# circuit.net
KiCad netlist of a schematic drawn in Altium Designer
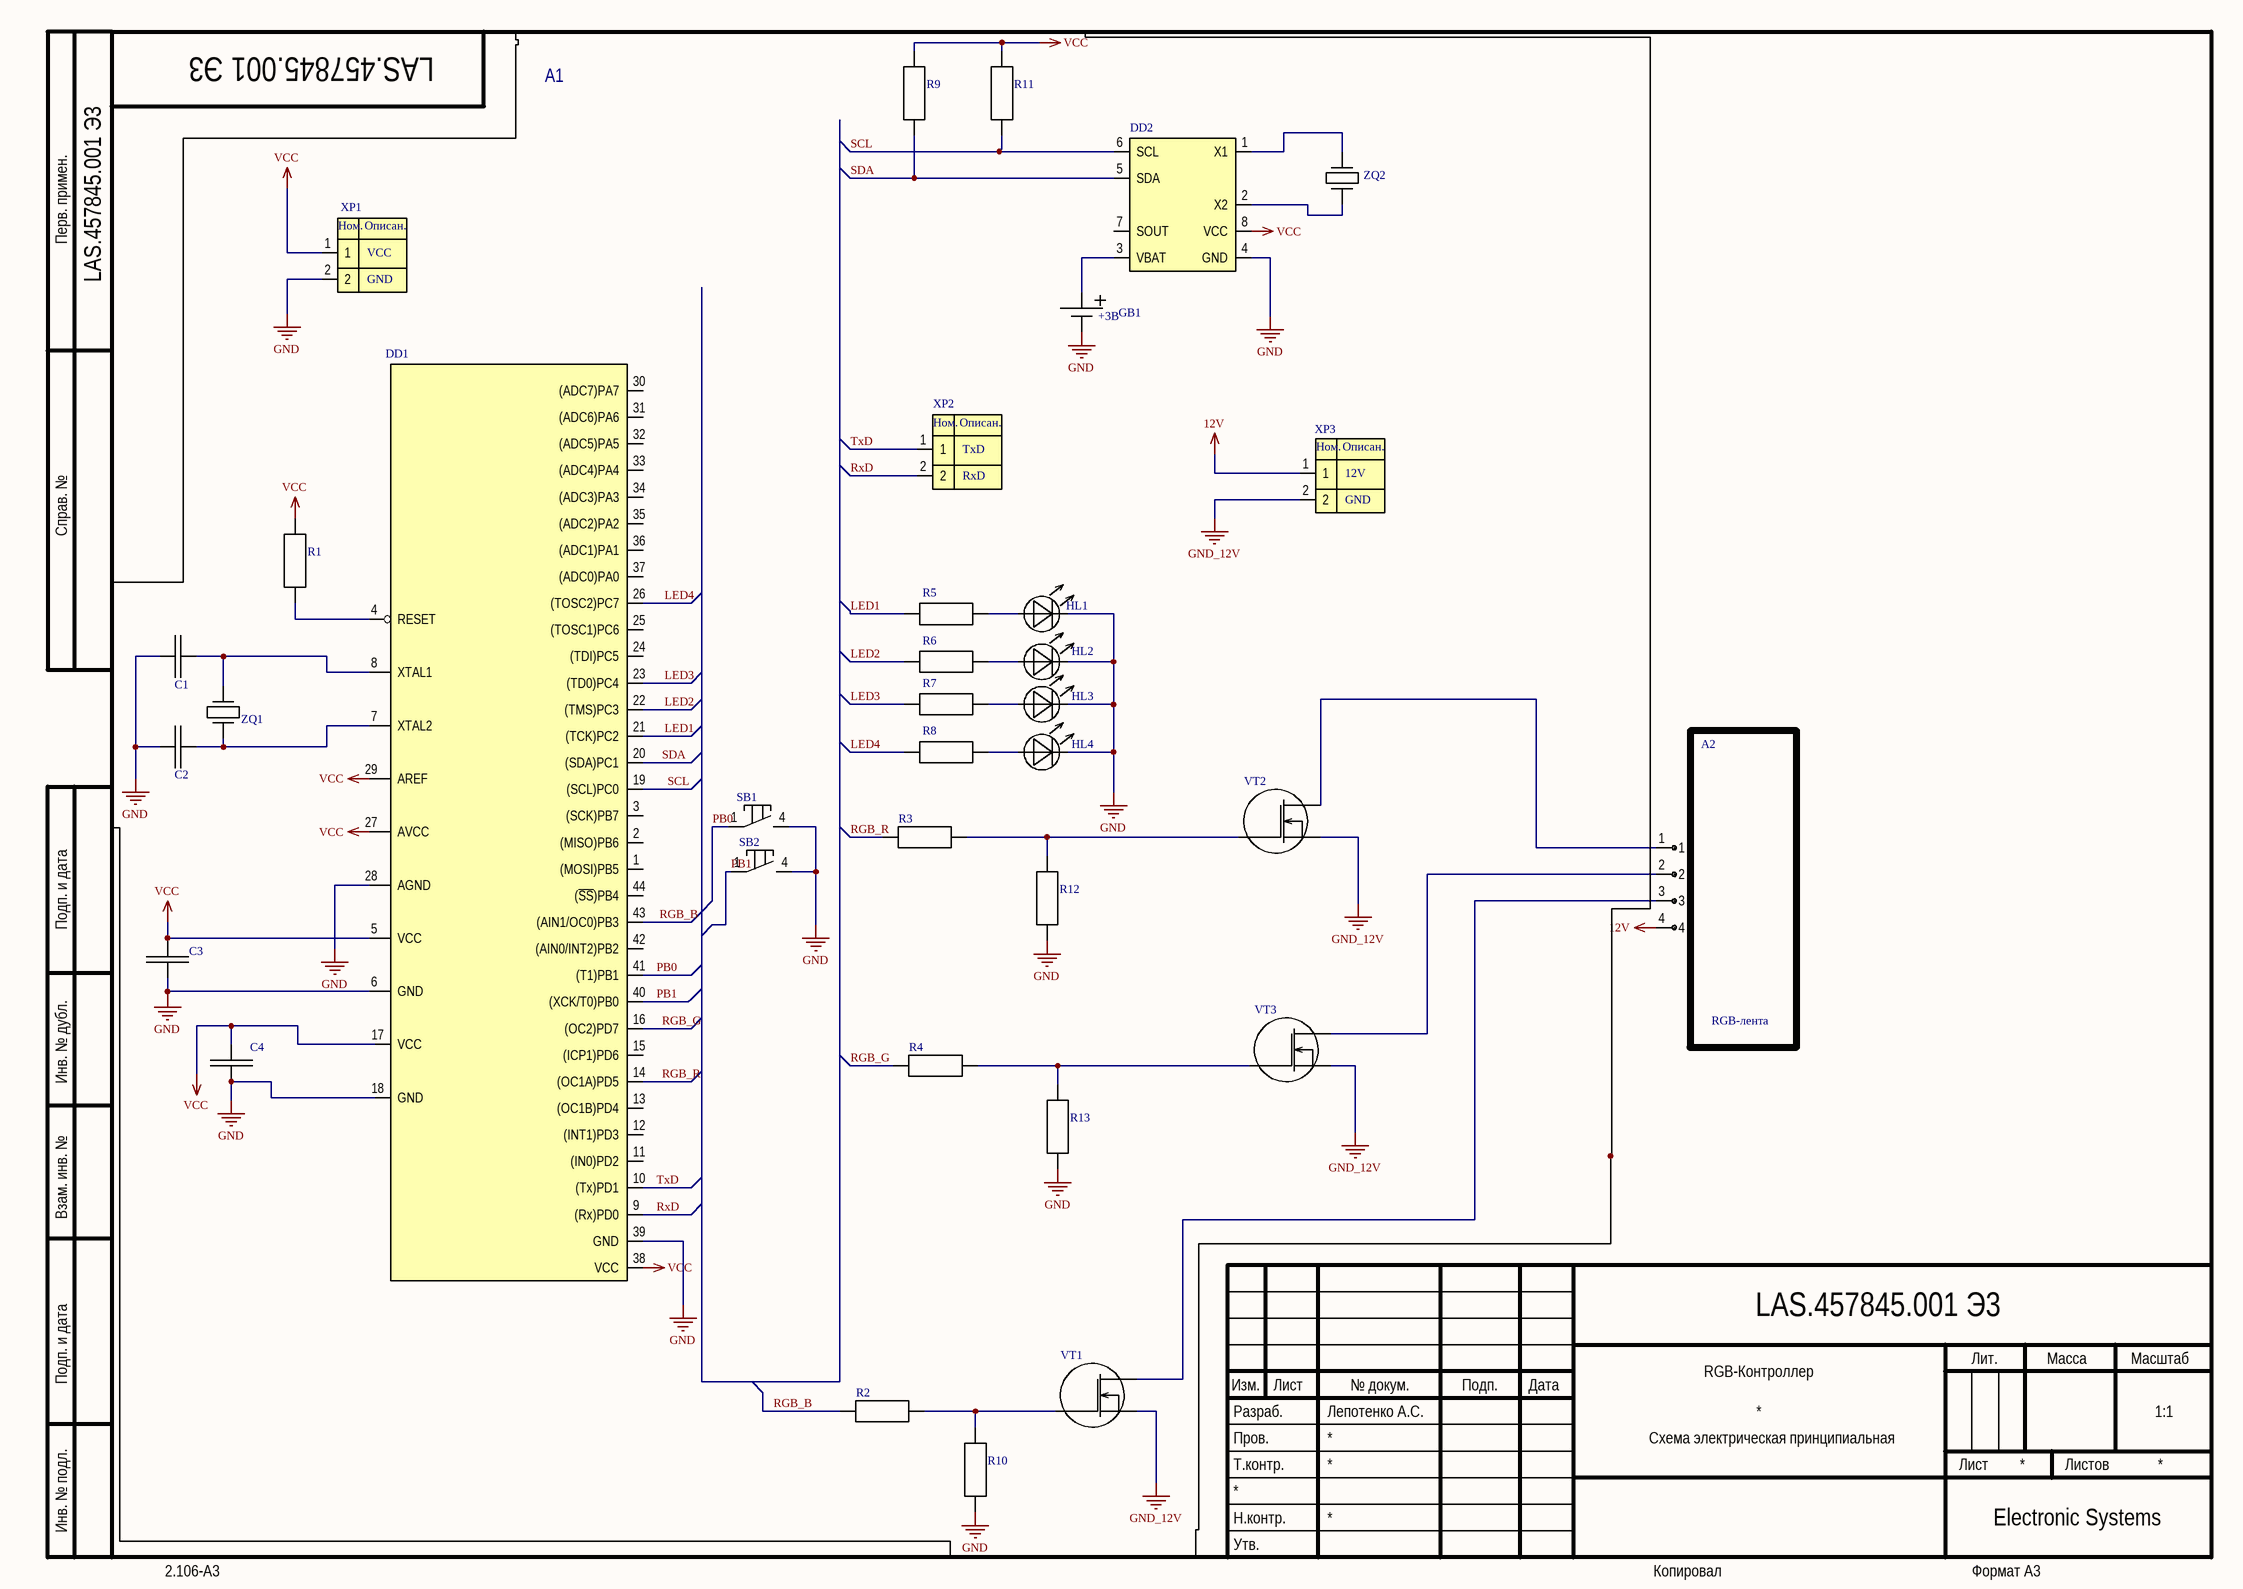
[diagram p0: circuit.SchDoc]

(export (version "E")
  (design (tool "Eeschema 10.0.6"))
  (components
    (comp (ref "C1")
      (value "Capasitor")
      (footprint "CAPC3216L")
      (libsource (lib "UGO_RGB") (part "Capasitor"))
    )
    (comp (ref "C2")
      (value "Capasitor")
      (footprint "CAPC3216L")
      (libsource (lib "UGO_RGB") (part "Capasitor"))
    )
    (comp (ref "C3")
      (value "Capasitor")
      (footprint "CAPC3216L")
      (libsource (lib "UGO_RGB") (part "Capasitor"))
    )
    (comp (ref "C4")
      (value "Capasitor")
      (footprint "CAPC3216L")
      (libsource (lib "UGO_RGB") (part "Capasitor"))
    )
    (comp (ref "DD1") (value "ATMega 16") (footprint "44A_M") (libsource (lib "UGO_RGB") (part "ATMega 16")))
    (comp (ref "DD2")
      (value "ds1307")
      (footprint "SOIC127P600X135-8N")
      (libsource (lib "UGO_RGB") (part "ds1307"))
    )
    (comp (ref "GB1") (value "Battery") (footprint "battery") (libsource (lib "UGO_RGB") (part "Battery")))
    (comp (ref "HL1") (value "LED") (footprint "GNLR") (libsource (lib "UGO_RGB") (part "LED")))
    (comp (ref "HL2") (value "LED") (footprint "GNLR") (libsource (lib "UGO_RGB") (part "LED")))
    (comp (ref "HL3") (value "LED") (footprint "GNLR") (libsource (lib "UGO_RGB") (part "LED")))
    (comp (ref "HL4") (value "LED") (footprint "GNLR") (libsource (lib "UGO_RGB") (part "LED")))
    (comp (ref "R1") (value "Resistor") (footprint "RESC3216M") (libsource (lib "UGO_RGB") (part "Resistor")))
    (comp (ref "R2") (value "Resistor") (footprint "RESC3216M") (libsource (lib "UGO_RGB") (part "Resistor")))
    (comp (ref "R3") (value "Resistor") (footprint "RESC3216M") (libsource (lib "UGO_RGB") (part "Resistor")))
    (comp (ref "R4") (value "Resistor") (footprint "RESC3216M") (libsource (lib "UGO_RGB") (part "Resistor")))
    (comp (ref "R5") (value "Resistor") (footprint "RESC3216M") (libsource (lib "UGO_RGB") (part "Resistor")))
    (comp (ref "R6") (value "Resistor") (footprint "RESC3216M") (libsource (lib "UGO_RGB") (part "Resistor")))
    (comp (ref "R7") (value "Resistor") (footprint "RESC3216M") (libsource (lib "UGO_RGB") (part "Resistor")))
    (comp (ref "R8") (value "Resistor") (footprint "RESC3216M") (libsource (lib "UGO_RGB") (part "Resistor")))
    (comp (ref "R9") (value "Resistor") (footprint "RESC3216M") (libsource (lib "UGO_RGB") (part "Resistor")))
    (comp (ref "R10")
      (value "Resistor")
      (footprint "RESC3216M")
      (libsource (lib "UGO_RGB") (part "Resistor"))
    )
    (comp (ref "R11")
      (value "Resistor")
      (footprint "RESC3216M")
      (libsource (lib "UGO_RGB") (part "Resistor"))
    )
    (comp (ref "R12")
      (value "Resistor")
      (footprint "RESC3216M")
      (libsource (lib "UGO_RGB") (part "Resistor"))
    )
    (comp (ref "R13")
      (value "Resistor")
      (footprint "RESC3216M")
      (libsource (lib "UGO_RGB") (part "Resistor"))
    )
    (comp (ref "RGB_Controller1")
      (value "RGB_Lent")
      (footprint "RGB")
      (libsource (lib "UGO_RGB") (part "RGB_Lent"))
    )
    (comp (ref "SB1")
      (value "button")
      (footprint "1102WD / 6x6x9,5 smd (T218)  технические характеристики скачать документацию (datasheet) по IT-1102WD / 6x6x9,5 smd")
      (libsource (lib "UGO_RGB") (part "button"))
    )
    (comp (ref "SB2")
      (value "button")
      (footprint "1102WD / 6x6x9,5 smd (T218)  технические характеристики скачать документацию (datasheet) по IT-1102WD / 6x6x9,5 smd")
      (libsource (lib "UGO_RGB") (part "button"))
    )
    (comp (ref "VT1") (value "IRZF44N") (footprint "TO-220") (libsource (lib "UGO_RGB") (part "IRZF44N")))
    (comp (ref "VT2") (value "IRZF44N") (footprint "TO-220") (libsource (lib "") (part "IRZF44N_1")))
    (comp (ref "VT3") (value "IRZF44N") (footprint "TO-220") (libsource (lib "") (part "IRZF44N_2")))
    (comp (ref "XP1")
      (value "Power Connector")
      (footprint "HB-2.0")
      (libsource (lib "UGO_RGB") (part "Power Connector"))
    )
    (comp (ref "XP2")
      (value "USART_connector")
      (footprint "pls-02")
      (libsource (lib "UGO_RGB") (part "USART_connector"))
    )
    (comp (ref "XP3") (value "Power 12V") (footprint "HB-2.0") (libsource (lib "UGO_RGB") (part "Power 12V")))
    (comp (ref "ZQ1")
      (value "Rezanator8M")
      (footprint "HC-49US")
      (libsource (lib "UGO_RGB") (part "Rezanator8M"))
    )
    (comp (ref "ZQ2")
      (value "Rezanator")
      (footprint "BCY-W2/D2.1")
      (libsource (lib "UGO_RGB") (part "Rezanator"))
    )
  )
  (nets
    (net (code "1") (name "/LED1") (class "Default")
      (node (ref "DD1") (pin "21") (pinfunction "(TCK)PC2_21") (pintype "passive"))
      (node (ref "R5") (pin "1") (pinfunction "1_1") (pintype "passive"))
    )
    (net (code "2") (name "/LED2") (class "Default")
      (node (ref "DD1") (pin "22") (pinfunction "(TMS)PC3_22") (pintype "passive"))
      (node (ref "R6") (pin "1") (pinfunction "1_1") (pintype "passive"))
    )
    (net (code "3") (name "/LED3") (class "Default")
      (node (ref "DD1") (pin "23") (pinfunction "(TD0)PC4_23") (pintype "passive"))
      (node (ref "R7") (pin "1") (pinfunction "1_1") (pintype "passive"))
    )
    (net (code "4") (name "/LED4") (class "Default")
      (node (ref "DD1") (pin "26") (pinfunction "(TOSC2)PC7_26") (pintype "passive"))
      (node (ref "R8") (pin "1") (pinfunction "1_1") (pintype "passive"))
    )
    (net (code "5") (name "/PB0") (class "Default")
      (node (ref "DD1") (pin "41") (pinfunction "(T1)PB1_41") (pintype "passive"))
      (node (ref "SB1") (pin "1") (pinfunction "1_1") (pintype "passive"))
    )
    (net (code "6") (name "/PB1") (class "Default")
      (node (ref "DD1") (pin "40") (pinfunction "(XCK/T0)PB0_40") (pintype "passive"))
      (node (ref "SB2") (pin "1") (pinfunction "1_1") (pintype "passive"))
    )
    (net (code "7") (name "/RGB_B") (class "Default")
      (node (ref "DD1") (pin "43") (pinfunction "(AIN1/OC0)PB3_43") (pintype "passive"))
      (node (ref "R2") (pin "1") (pinfunction "1_1") (pintype "passive"))
    )
    (net (code "8") (name "/RGB_G") (class "Default")
      (node (ref "DD1") (pin "16") (pinfunction "(OC2)PD7_16") (pintype "passive"))
      (node (ref "R4") (pin "1") (pinfunction "1_1") (pintype "passive"))
    )
    (net (code "9") (name "/RGB_R") (class "Default")
      (node (ref "DD1") (pin "14") (pinfunction "(OC1A)PD5_14") (pintype "passive"))
      (node (ref "R3") (pin "1") (pinfunction "1_1") (pintype "passive"))
    )
    (net (code "10") (name "/RxD") (class "Default")
      (node (ref "DD1") (pin "9") (pinfunction "(Rx)PD0_9") (pintype "passive"))
      (node (ref "XP2") (pin "2") (pinfunction "2_2") (pintype "passive"))
    )
    (net (code "11") (name "/SCL") (class "Default")
      (node (ref "DD1") (pin "19") (pinfunction "(SCL)PC0_19") (pintype "passive"))
      (node (ref "DD2") (pin "6") (pinfunction "SCL_6") (pintype "passive"))
      (node (ref "R11") (pin "1") (pinfunction "1_1") (pintype "passive"))
    )
    (net (code "12") (name "/SDA") (class "Default")
      (node (ref "DD1") (pin "20") (pinfunction "(SDA)PC1_20") (pintype "passive"))
      (node (ref "DD2") (pin "5") (pinfunction "SDA_5") (pintype "passive"))
      (node (ref "R9") (pin "1") (pinfunction "1_1") (pintype "passive"))
    )
    (net (code "13") (name "/TxD") (class "Default")
      (node (ref "DD1") (pin "10") (pinfunction "(Tx)PD1_10") (pintype "passive"))
      (node (ref "XP2") (pin "1") (pinfunction "1_1") (pintype "passive"))
    )
    (net (code "14") (name "12V") (class "Default")
      (node (ref "RGB_Controller1") (pin "4") (pinfunction "4_4") (pintype "passive"))
      (node (ref "XP3") (pin "1") (pinfunction "1_1") (pintype "passive"))
    )
    (net (code "15") (name "GND") (class "Default")
      (node (ref "C1") (pin "1") (pinfunction "1_1") (pintype "passive"))
      (node (ref "C2") (pin "1") (pinfunction "1_1") (pintype "passive"))
      (node (ref "C3") (pin "1") (pinfunction "1_1") (pintype "passive"))
      (node (ref "C4") (pin "1") (pinfunction "1_1") (pintype "passive"))
      (node (ref "DD1") (pin "18") (pinfunction "GND_18") (pintype "passive"))
      (node (ref "DD1") (pin "28") (pinfunction "AGND_28") (pintype "passive"))
      (node (ref "DD1") (pin "39") (pinfunction "GND_39") (pintype "passive"))
      (node (ref "DD1") (pin "6") (pinfunction "GND_6") (pintype "passive"))
      (node (ref "DD2") (pin "4") (pinfunction "GND_4") (pintype "passive"))
      (node (ref "GB1") (pin "2") (pinfunction "2_2") (pintype "passive"))
      (node (ref "HL1") (pin "2") (pinfunction "2_2") (pintype "passive"))
      (node (ref "HL2") (pin "2") (pinfunction "2_2") (pintype "passive"))
      (node (ref "HL3") (pin "2") (pinfunction "2_2") (pintype "passive"))
      (node (ref "HL4") (pin "2") (pinfunction "2_2") (pintype "passive"))
      (node (ref "R10") (pin "1") (pinfunction "1_1") (pintype "passive"))
      (node (ref "R12") (pin "1") (pinfunction "1_1") (pintype "passive"))
      (node (ref "R13") (pin "1") (pinfunction "1_1") (pintype "passive"))
      (node (ref "SB1") (pin "4") (pinfunction "4_4") (pintype "passive"))
      (node (ref "SB2") (pin "4") (pinfunction "4_4") (pintype "passive"))
      (node (ref "XP1") (pin "2") (pinfunction "2_2") (pintype "passive"))
    )
    (net (code "16") (name "GND_12V") (class "Default")
      (node (ref "VT1") (pin "3") (pinfunction "Source_3") (pintype "passive"))
      (node (ref "VT2") (pin "3") (pinfunction "Source_3") (pintype "passive"))
      (node (ref "VT3") (pin "3") (pinfunction "Source_3") (pintype "passive"))
      (node (ref "XP3") (pin "2") (pinfunction "2_2") (pintype "passive"))
    )
    (net (code "17") (name "Net-(DD1-RESET)") (class "Default")
      (node (ref "DD1") (pin "4") (pinfunction "RESET_4") (pintype "passive"))
      (node (ref "R1") (pin "1") (pinfunction "1_1") (pintype "passive"))
    )
    (net (code "18") (name "Net-(DD1-XTAL1)") (class "Default")
      (node (ref "C1") (pin "2") (pinfunction "2_2") (pintype "passive"))
      (node (ref "DD1") (pin "8") (pinfunction "XTAL1_8") (pintype "passive"))
      (node (ref "ZQ1") (pin "1") (pinfunction "1_1") (pintype "passive"))
    )
    (net (code "19") (name "Net-(DD1-XTAL2)") (class "Default")
      (node (ref "C2") (pin "2") (pinfunction "2_2") (pintype "passive"))
      (node (ref "DD1") (pin "7") (pinfunction "XTAL2_7") (pintype "passive"))
      (node (ref "ZQ1") (pin "2") (pinfunction "2_2") (pintype "passive"))
    )
    (net (code "20") (name "Net-(DD2-VBAT)") (class "Default")
      (node (ref "DD2") (pin "3") (pinfunction "VBAT_3") (pintype "passive"))
      (node (ref "GB1") (pin "1") (pinfunction "1_1") (pintype "passive"))
    )
    (net (code "21") (name "Net-(DD2-X1)") (class "Default")
      (node (ref "DD2") (pin "1") (pinfunction "X1_1") (pintype "passive"))
      (node (ref "ZQ2") (pin "2") (pinfunction "2_2") (pintype "passive"))
    )
    (net (code "22") (name "Net-(DD2-X2)") (class "Default")
      (node (ref "DD2") (pin "2") (pinfunction "X2_2") (pintype "passive"))
      (node (ref "ZQ2") (pin "1") (pinfunction "1_1") (pintype "passive"))
    )
    (net (code "23") (name "Net-(HL1-Pad1)") (class "Default")
      (node (ref "HL1") (pin "1") (pinfunction "1_1") (pintype "passive"))
      (node (ref "R5") (pin "2") (pinfunction "2_2") (pintype "passive"))
    )
    (net (code "24") (name "Net-(HL2-Pad1)") (class "Default")
      (node (ref "HL2") (pin "1") (pinfunction "1_1") (pintype "passive"))
      (node (ref "R6") (pin "2") (pinfunction "2_2") (pintype "passive"))
    )
    (net (code "25") (name "Net-(HL3-Pad1)") (class "Default")
      (node (ref "HL3") (pin "1") (pinfunction "1_1") (pintype "passive"))
      (node (ref "R7") (pin "2") (pinfunction "2_2") (pintype "passive"))
    )
    (net (code "26") (name "Net-(HL4-Pad1)") (class "Default")
      (node (ref "HL4") (pin "1") (pinfunction "1_1") (pintype "passive"))
      (node (ref "R8") (pin "2") (pinfunction "2_2") (pintype "passive"))
    )
    (net (code "27") (name "Net-(VT1-D)") (class "Default")
      (node (ref "RGB_Controller1") (pin "3") (pinfunction "3_3") (pintype "passive"))
      (node (ref "VT1") (pin "2") (pinfunction "D_2") (pintype "passive"))
    )
    (net (code "28") (name "Net-(VT1-G)") (class "Default")
      (node (ref "R10") (pin "2") (pinfunction "2_2") (pintype "passive"))
      (node (ref "R2") (pin "2") (pinfunction "2_2") (pintype "passive"))
      (node (ref "VT1") (pin "1") (pinfunction "G_1") (pintype "passive"))
    )
    (net (code "29") (name "Net-(VT2-D)") (class "Default")
      (node (ref "RGB_Controller1") (pin "1") (pinfunction "1_1") (pintype "passive"))
      (node (ref "VT2") (pin "2") (pinfunction "D_2") (pintype "passive"))
    )
    (net (code "30") (name "Net-(VT2-G)") (class "Default")
      (node (ref "R12") (pin "2") (pinfunction "2_2") (pintype "passive"))
      (node (ref "R3") (pin "2") (pinfunction "2_2") (pintype "passive"))
      (node (ref "VT2") (pin "1") (pinfunction "G_1") (pintype "passive"))
    )
    (net (code "31") (name "Net-(VT3-D)") (class "Default")
      (node (ref "RGB_Controller1") (pin "2") (pinfunction "2_2") (pintype "passive"))
      (node (ref "VT3") (pin "2") (pinfunction "D_2") (pintype "passive"))
    )
    (net (code "32") (name "Net-(VT3-G)") (class "Default")
      (node (ref "R13") (pin "2") (pinfunction "2_2") (pintype "passive"))
      (node (ref "R4") (pin "2") (pinfunction "2_2") (pintype "passive"))
      (node (ref "VT3") (pin "1") (pinfunction "G_1") (pintype "passive"))
    )
    (net (code "33") (name "VCC") (class "Default")
      (node (ref "C3") (pin "2") (pinfunction "2_2") (pintype "passive"))
      (node (ref "C4") (pin "2") (pinfunction "2_2") (pintype "passive"))
      (node (ref "DD1") (pin "17") (pinfunction "VCC_17") (pintype "passive"))
      (node (ref "DD1") (pin "27") (pinfunction "AVCC_27") (pintype "passive"))
      (node (ref "DD1") (pin "29") (pinfunction "AREF_29") (pintype "passive"))
      (node (ref "DD1") (pin "38") (pinfunction "VCC_38") (pintype "passive"))
      (node (ref "DD1") (pin "5") (pinfunction "VCC_5") (pintype "passive"))
      (node (ref "DD2") (pin "8") (pinfunction "VCC_8") (pintype "passive"))
      (node (ref "R1") (pin "2") (pinfunction "2_2") (pintype "passive"))
      (node (ref "R11") (pin "2") (pinfunction "2_2") (pintype "passive"))
      (node (ref "R9") (pin "2") (pinfunction "2_2") (pintype "passive"))
      (node (ref "XP1") (pin "1") (pinfunction "1_1") (pintype "passive"))
    )
    (net (code "34") (name "unconnected-(DD1-(ADC0)PA0-Pad37)") (class "Default")
      (node (ref "DD1") (pin "37") (pinfunction "(ADC0)PA0_37") (pintype "passive"))
    )
    (net (code "35") (name "unconnected-(DD1-(ADC1)PA1-Pad36)") (class "Default")
      (node (ref "DD1") (pin "36") (pinfunction "(ADC1)PA1_36") (pintype "passive"))
    )
    (net (code "36") (name "unconnected-(DD1-(ADC2)PA2-Pad35)") (class "Default")
      (node (ref "DD1") (pin "35") (pinfunction "(ADC2)PA2_35") (pintype "passive"))
    )
    (net (code "37") (name "unconnected-(DD1-(ADC3)PA3-Pad34)") (class "Default")
      (node (ref "DD1") (pin "34") (pinfunction "(ADC3)PA3_34") (pintype "passive"))
    )
    (net (code "38") (name "unconnected-(DD1-(ADC4)PA4-Pad33)") (class "Default")
      (node (ref "DD1") (pin "33") (pinfunction "(ADC4)PA4_33") (pintype "passive"))
    )
    (net (code "39") (name "unconnected-(DD1-(ADC5)PA5-Pad32)") (class "Default")
      (node (ref "DD1") (pin "32") (pinfunction "(ADC5)PA5_32") (pintype "passive"))
    )
    (net (code "40") (name "unconnected-(DD1-(ADC6)PA6-Pad31)") (class "Default")
      (node (ref "DD1") (pin "31") (pinfunction "(ADC6)PA6_31") (pintype "passive"))
    )
    (net (code "41") (name "unconnected-(DD1-(ADC7)PA7-Pad30)") (class "Default")
      (node (ref "DD1") (pin "30") (pinfunction "(ADC7)PA7_30") (pintype "passive"))
    )
    (net (code "42") (name "unconnected-(DD1-(AIN0{slash}INT2)PB2-Pad42)") (class "Default")
      (node (ref "DD1") (pin "42") (pinfunction "(AIN0/INT2)PB2_42") (pintype "passive"))
    )
    (net (code "43") (name "unconnected-(DD1-(ICP1)PD6-Pad15)") (class "Default")
      (node (ref "DD1") (pin "15") (pinfunction "(ICP1)PD6_15") (pintype "passive"))
    )
    (net (code "44") (name "unconnected-(DD1-(IN0)PD2-Pad11)") (class "Default")
      (node (ref "DD1") (pin "11") (pinfunction "(IN0)PD2_11") (pintype "passive"))
    )
    (net (code "45") (name "unconnected-(DD1-(INT1)PD3-Pad12)") (class "Default")
      (node (ref "DD1") (pin "12") (pinfunction "(INT1)PD3_12") (pintype "passive"))
    )
    (net (code "46") (name "unconnected-(DD1-(MISO)PB6-Pad2)") (class "Default")
      (node (ref "DD1") (pin "2") (pinfunction "(MISO)PB6_2") (pintype "passive"))
    )
    (net (code "47") (name "unconnected-(DD1-(MOSI)PB5-Pad1)") (class "Default")
      (node (ref "DD1") (pin "1") (pinfunction "(MOSI)PB5_1") (pintype "passive"))
    )
    (net (code "48") (name "unconnected-(DD1-(OC1B)PD4-Pad13)") (class "Default")
      (node (ref "DD1") (pin "13") (pinfunction "(OC1B)PD4_13") (pintype "passive"))
    )
    (net (code "49") (name "unconnected-(DD1-(SCK)PB7-Pad3)") (class "Default")
      (node (ref "DD1") (pin "3") (pinfunction "(SCK)PB7_3") (pintype "passive"))
    )
    (net (code "50") (name "unconnected-(DD1-(TDI)PC5-Pad24)") (class "Default")
      (node (ref "DD1") (pin "24") (pinfunction "(TDI)PC5_24") (pintype "passive"))
    )
    (net (code "51") (name "unconnected-(DD1-(TOSC1)PC6-Pad25)") (class "Default")
      (node (ref "DD1") (pin "25") (pinfunction "(TOSC1)PC6_25") (pintype "passive"))
    )
    (net (code "52") (name "unconnected-(DD1-(~{SS})PB4-Pad44)") (class "Default")
      (node (ref "DD1") (pin "44") (pinfunction "(~{SS})PB4_44") (pintype "passive"))
    )
    (net (code "53") (name "unconnected-(DD2-SOUT-Pad7)") (class "Default")
      (node (ref "DD2") (pin "7") (pinfunction "SOUT_7") (pintype "passive"))
    )
  )
)
